# Aquila-2018-Under-DESKTOP-4DKEQLF.net
KiCad netlist of a schematic drawn in EAGLE
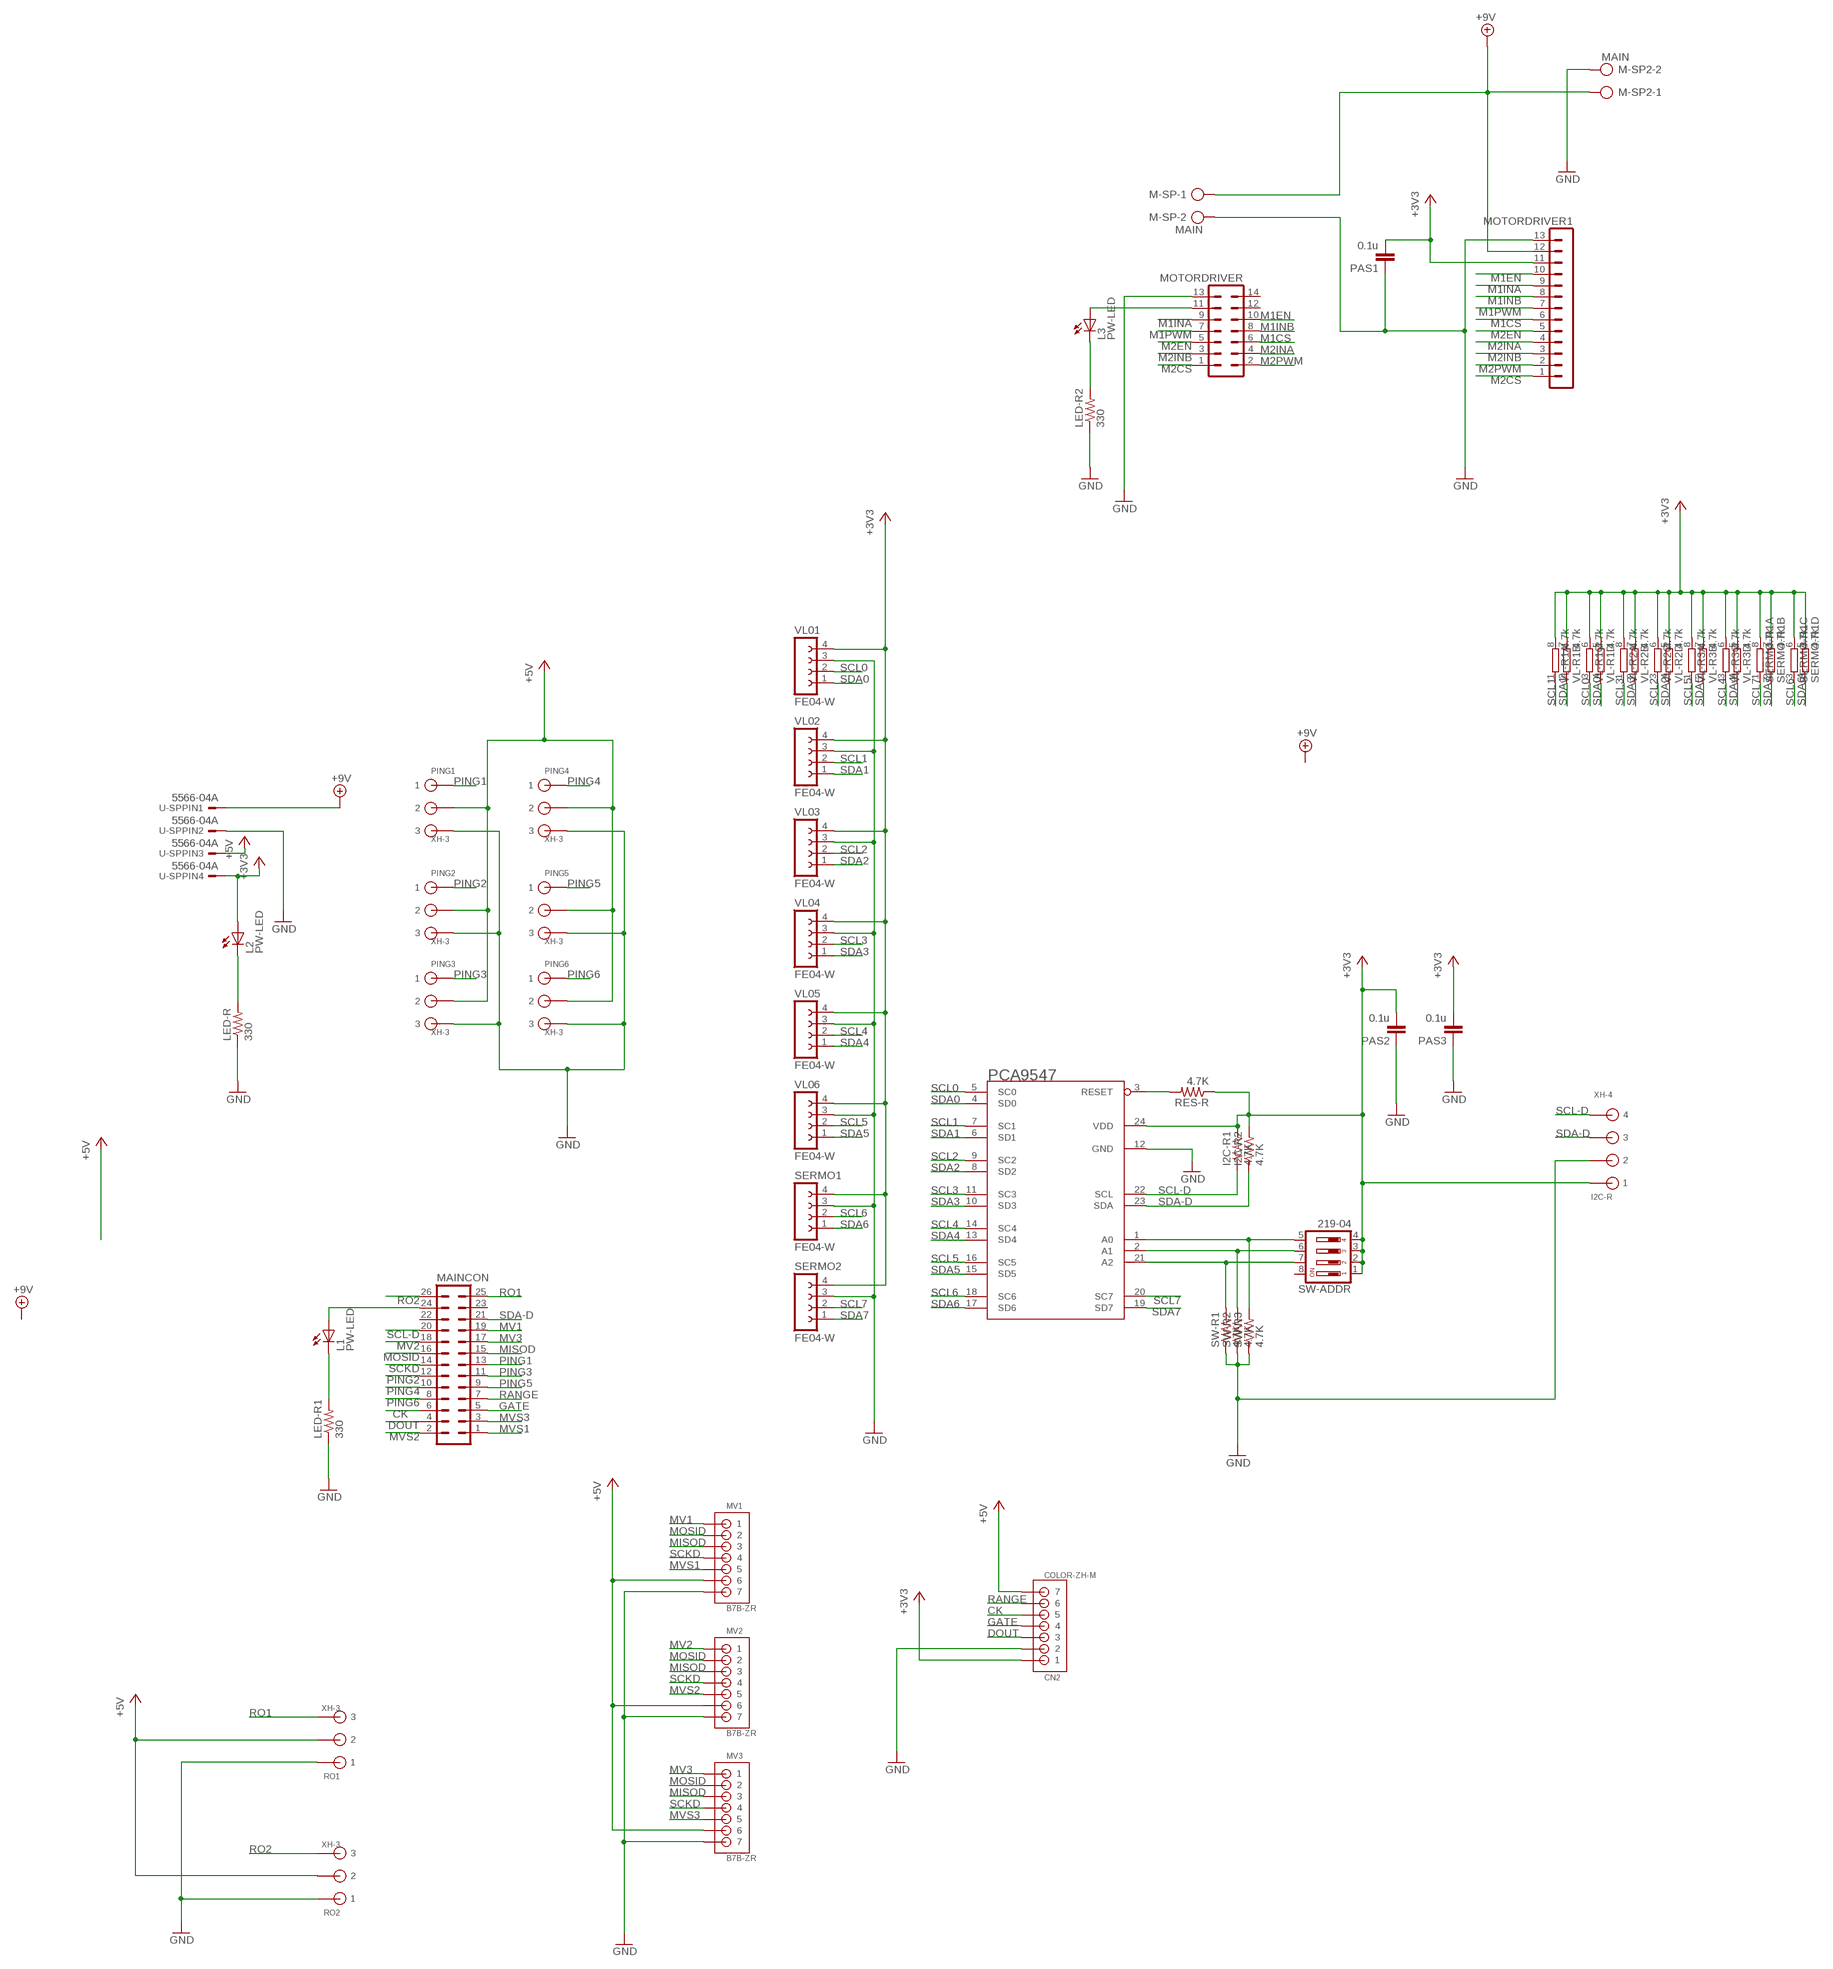
[diagram p0: schematic, sheet 1]

(export (version "E")
  (design (tool "Eeschema 10.0.6"))
  (components
    (comp (ref "CN2")
      (value "COLOR-ZH-M")
      (footprint "eagle-import:B7B-ZR")
      (libsource (lib "eagle-import") (part "B7B-ZR"))
    )
    (comp (ref "I2C-R")
      (value "XH-4")
      (footprint "eagle-import:CON4")
      (libsource (lib "eagle-import") (part "XH-4"))
    )
    (comp (ref "I2C-R1")
      (value "4.7K")
      (footprint "eagle-import:R0805")
      (libsource (lib "eagle-import") (part "R-US_R0805"))
    )
    (comp (ref "I2C-R2")
      (value "4.7K")
      (footprint "eagle-import:R0805")
      (libsource (lib "eagle-import") (part "R-US_R0805"))
    )
    (comp (ref "L1")
      (value "PW-LED")
      (footprint "eagle-import:CHIPLED_0805")
      (libsource (lib "eagle-import") (part "LEDCHIPLED_0805"))
    )
    (comp (ref "L2")
      (value "PW-LED")
      (footprint "eagle-import:CHIPLED_0805")
      (libsource (lib "eagle-import") (part "LEDCHIPLED_0805"))
    )
    (comp (ref "L3")
      (value "PW-LED")
      (footprint "eagle-import:CHIPLED_0805")
      (libsource (lib "eagle-import") (part "LEDCHIPLED_0805"))
    )
    (comp (ref "LED-R")
      (value "330")
      (footprint "eagle-import:R0805")
      (libsource (lib "eagle-import") (part "R-US_R0805"))
    )
    (comp (ref "LED-R1")
      (value "330")
      (footprint "eagle-import:R0805")
      (libsource (lib "eagle-import") (part "R-US_R0805"))
    )
    (comp (ref "LED-R2")
      (value "330")
      (footprint "eagle-import:R0805")
      (libsource (lib "eagle-import") (part "R-US_R0805"))
    )
    (comp (ref "M-SP")
      (value "MAIN")
      (footprint "eagle-import:AK500_2")
      (libsource (lib "eagle-import") (part "AK500/2"))
    )
    (comp (ref "M-SP2")
      (value "MAIN")
      (footprint "eagle-import:AK500_2")
      (libsource (lib "eagle-import") (part "AK500/2"))
    )
    (comp (ref "MAINCON")
      (value "ML26")
      (footprint "eagle-import:ML26")
      (libsource (lib "eagle-import") (part "ML26"))
    )
    (comp (ref "MOTORDRIVER")
      (value "ML14")
      (footprint "eagle-import:ML14")
      (libsource (lib "eagle-import") (part "ML14"))
    )
    (comp (ref "MOTORDRIVER1")
      (value "MA13-1")
      (footprint "eagle-import:MA13-1")
      (libsource (lib "eagle-import") (part "MA13-1"))
    )
    (comp (ref "MV1")
      (value "B7B-ZR")
      (footprint "eagle-import:B7B-ZR")
      (libsource (lib "eagle-import") (part "B7B-ZR"))
    )
    (comp (ref "MV2")
      (value "B7B-ZR")
      (footprint "eagle-import:B7B-ZR")
      (libsource (lib "eagle-import") (part "B7B-ZR"))
    )
    (comp (ref "MV3")
      (value "B7B-ZR")
      (footprint "eagle-import:B7B-ZR")
      (libsource (lib "eagle-import") (part "B7B-ZR"))
    )
    (comp (ref "PAS1")
      (value "0.1u")
      (footprint "eagle-import:C0805")
      (fields (field (name "SPICEPREFIX") "B"))
      (libsource (lib "eagle-import") (part "C-EUC0805"))
    )
    (comp (ref "PAS2")
      (value "0.1u")
      (footprint "eagle-import:C0805")
      (fields (field (name "SPICEPREFIX") "B"))
      (libsource (lib "eagle-import") (part "C-EUC0805"))
    )
    (comp (ref "PAS3")
      (value "0.1u")
      (footprint "eagle-import:C0805")
      (fields (field (name "SPICEPREFIX") "B"))
      (libsource (lib "eagle-import") (part "C-EUC0805"))
    )
    (comp (ref "PCA9547")
      (value "PCA9547")
      (footprint "eagle-import:SO24L")
      (libsource (lib "eagle-import") (part "PCA9547"))
    )
    (comp (ref "PING1")
      (value "XH-3")
      (footprint "eagle-import:CON3")
      (libsource (lib "eagle-import") (part "XH-3"))
    )
    (comp (ref "PING2")
      (value "XH-3")
      (footprint "eagle-import:CON3")
      (libsource (lib "eagle-import") (part "XH-3"))
    )
    (comp (ref "PING3")
      (value "XH-3")
      (footprint "eagle-import:CON3")
      (libsource (lib "eagle-import") (part "XH-3"))
    )
    (comp (ref "PING4")
      (value "XH-3")
      (footprint "eagle-import:CON3")
      (libsource (lib "eagle-import") (part "XH-3"))
    )
    (comp (ref "PING5")
      (value "XH-3")
      (footprint "eagle-import:CON3")
      (libsource (lib "eagle-import") (part "XH-3"))
    )
    (comp (ref "PING6")
      (value "XH-3")
      (footprint "eagle-import:CON3")
      (libsource (lib "eagle-import") (part "XH-3"))
    )
    (comp (ref "RES-R")
      (value "4.7K")
      (footprint "eagle-import:R0805")
      (libsource (lib "eagle-import") (part "R-US_R0805"))
    )
    (comp (ref "RO1")
      (value "XH-3")
      (footprint "eagle-import:CON3")
      (libsource (lib "eagle-import") (part "forprint_XH-3"))
    )
    (comp (ref "RO2")
      (value "XH-3")
      (footprint "eagle-import:CON3")
      (libsource (lib "eagle-import") (part "forprint_XH-3"))
    )
    (comp (ref "SERMO-R1")
      (value "4.7k")
      (footprint "eagle-import:EXB28V")
      (libsource (lib "eagle-import") (part "4R-NEXB28V"))
    )
    (comp (ref "SERMO1")
      (value "FE04-W")
      (footprint "eagle-import:FE04-W")
      (libsource (lib "eagle-import") (part "FE04-W"))
    )
    (comp (ref "SERMO2")
      (value "FE04-W")
      (footprint "eagle-import:FE04-W")
      (libsource (lib "eagle-import") (part "FE04-W"))
    )
    (comp (ref "SW-ADDR")
      (value "219-04")
      (footprint "eagle-import:CTS-219-04")
      (libsource (lib "eagle-import") (part "219-04"))
    )
    (comp (ref "SW-R1")
      (value "4.7K")
      (footprint "eagle-import:R0805")
      (libsource (lib "eagle-import") (part "R-US_R0805"))
    )
    (comp (ref "SW-R2")
      (value "4.7K")
      (footprint "eagle-import:R0805")
      (libsource (lib "eagle-import") (part "R-US_R0805"))
    )
    (comp (ref "SW-R3")
      (value "4.7K")
      (footprint "eagle-import:R0805")
      (libsource (lib "eagle-import") (part "R-US_R0805"))
    )
    (comp (ref "U-SP")
      (value "5566-04A")
      (footprint "eagle-import:5566-04A")
      (libsource (lib "eagle-import") (part "5566-04A"))
    )
    (comp (ref "VL-R1")
      (value "4.7k")
      (footprint "eagle-import:EXB28V")
      (libsource (lib "eagle-import") (part "4R-NEXB28V"))
    )
    (comp (ref "VL-R2")
      (value "4.7k")
      (footprint "eagle-import:EXB28V")
      (libsource (lib "eagle-import") (part "4R-NEXB28V"))
    )
    (comp (ref "VL-R3")
      (value "4.7k")
      (footprint "eagle-import:EXB28V")
      (libsource (lib "eagle-import") (part "4R-NEXB28V"))
    )
    (comp (ref "VL01")
      (value "FE04-W")
      (footprint "eagle-import:FE04-W")
      (libsource (lib "eagle-import") (part "FE04-W"))
    )
    (comp (ref "VL02")
      (value "FE04-W")
      (footprint "eagle-import:FE04-W")
      (libsource (lib "eagle-import") (part "FE04-W"))
    )
    (comp (ref "VL03")
      (value "FE04-W")
      (footprint "eagle-import:FE04-W")
      (libsource (lib "eagle-import") (part "FE04-W"))
    )
    (comp (ref "VL04")
      (value "FE04-W")
      (footprint "eagle-import:FE04-W")
      (libsource (lib "eagle-import") (part "FE04-W"))
    )
    (comp (ref "VL05")
      (value "FE04-W")
      (footprint "eagle-import:FE04-W")
      (libsource (lib "eagle-import") (part "FE04-W"))
    )
    (comp (ref "VL06")
      (value "FE04-W")
      (footprint "eagle-import:FE04-W")
      (libsource (lib "eagle-import") (part "FE04-W"))
    )
  )
  (nets
    (net (code "1") (name "+3V3") (class "Default")
      (node (ref "CN2") (pin "1") (pinfunction "1_1") (pintype "bidirectional"))
      (node (ref "I2C-R") (pin "P$1") (pinfunction "1_P$1") (pintype "bidirectional"))
      (node (ref "I2C-R1") (pin "2") (pinfunction "2_2") (pintype "passive"))
      (node (ref "I2C-R2") (pin "2") (pinfunction "2_2") (pintype "passive"))
      (node (ref "L2") (pin "A") (pinfunction "A_A") (pintype "passive"))
      (node (ref "MOTORDRIVER1") (pin "11") (pinfunction "11_11") (pintype "passive"))
      (node (ref "PAS1") (pin "2") (pinfunction "2_2") (pintype "passive"))
      (node (ref "PAS2") (pin "2") (pinfunction "2_2") (pintype "passive"))
      (node (ref "PAS3") (pin "2") (pinfunction "2_2") (pintype "passive"))
      (node (ref "PCA9547") (pin "24") (pinfunction "VDD_24") (pintype "power_in"))
      (node (ref "RES-R") (pin "1") (pinfunction "1_1") (pintype "passive"))
      (node (ref "SERMO-R1") (pin "5") (pinfunction "2_5") (pintype "passive"))
      (node (ref "SERMO-R1") (pin "6") (pinfunction "2_6") (pintype "passive"))
      (node (ref "SERMO-R1") (pin "7") (pinfunction "2_7") (pintype "passive"))
      (node (ref "SERMO-R1") (pin "8") (pinfunction "2_8") (pintype "passive"))
      (node (ref "SERMO1") (pin "4") (pinfunction "4_4") (pintype "passive"))
      (node (ref "SERMO2") (pin "4") (pinfunction "4_4") (pintype "passive"))
      (node (ref "SW-ADDR") (pin "1") (pinfunction "1_1") (pintype "passive"))
      (node (ref "SW-ADDR") (pin "2") (pinfunction "2_2") (pintype "passive"))
      (node (ref "SW-ADDR") (pin "3") (pinfunction "3_3") (pintype "passive"))
      (node (ref "SW-ADDR") (pin "4") (pinfunction "4_4") (pintype "passive"))
      (node (ref "U-SP") (pin "4") (pinfunction "S_4") (pintype "passive"))
      (node (ref "VL-R1") (pin "5") (pinfunction "2_5") (pintype "passive"))
      (node (ref "VL-R1") (pin "6") (pinfunction "2_6") (pintype "passive"))
      (node (ref "VL-R1") (pin "7") (pinfunction "2_7") (pintype "passive"))
      (node (ref "VL-R1") (pin "8") (pinfunction "2_8") (pintype "passive"))
      (node (ref "VL-R2") (pin "5") (pinfunction "2_5") (pintype "passive"))
      (node (ref "VL-R2") (pin "6") (pinfunction "2_6") (pintype "passive"))
      (node (ref "VL-R2") (pin "7") (pinfunction "2_7") (pintype "passive"))
      (node (ref "VL-R2") (pin "8") (pinfunction "2_8") (pintype "passive"))
      (node (ref "VL-R3") (pin "5") (pinfunction "2_5") (pintype "passive"))
      (node (ref "VL-R3") (pin "6") (pinfunction "2_6") (pintype "passive"))
      (node (ref "VL-R3") (pin "7") (pinfunction "2_7") (pintype "passive"))
      (node (ref "VL-R3") (pin "8") (pinfunction "2_8") (pintype "passive"))
      (node (ref "VL01") (pin "4") (pinfunction "4_4") (pintype "passive"))
      (node (ref "VL02") (pin "4") (pinfunction "4_4") (pintype "passive"))
      (node (ref "VL03") (pin "4") (pinfunction "4_4") (pintype "passive"))
      (node (ref "VL04") (pin "4") (pinfunction "4_4") (pintype "passive"))
      (node (ref "VL05") (pin "4") (pinfunction "4_4") (pintype "passive"))
      (node (ref "VL06") (pin "4") (pinfunction "4_4") (pintype "passive"))
    )
    (net (code "2") (name "+5V") (class "Default")
      (node (ref "CN2") (pin "7") (pinfunction "7_7") (pintype "bidirectional"))
      (node (ref "MV1") (pin "6") (pinfunction "6_6") (pintype "bidirectional"))
      (node (ref "MV2") (pin "6") (pinfunction "6_6") (pintype "bidirectional"))
      (node (ref "MV3") (pin "6") (pinfunction "6_6") (pintype "bidirectional"))
      (node (ref "PING1") (pin "P$2") (pinfunction "2_P$2") (pintype "bidirectional"))
      (node (ref "PING2") (pin "P$2") (pinfunction "2_P$2") (pintype "bidirectional"))
      (node (ref "PING3") (pin "P$2") (pinfunction "2_P$2") (pintype "bidirectional"))
      (node (ref "PING4") (pin "P$2") (pinfunction "2_P$2") (pintype "bidirectional"))
      (node (ref "PING5") (pin "P$2") (pinfunction "2_P$2") (pintype "bidirectional"))
      (node (ref "PING6") (pin "P$2") (pinfunction "2_P$2") (pintype "bidirectional"))
      (node (ref "RO1") (pin "P$2") (pinfunction "2_P$2") (pintype "bidirectional"))
      (node (ref "RO2") (pin "P$2") (pinfunction "2_P$2") (pintype "bidirectional"))
      (node (ref "U-SP") (pin "3") (pinfunction "S_3") (pintype "passive"))
    )
    (net (code "3") (name "+9V") (class "Default")
      (node (ref "M-SP") (pin "1") (pinfunction "KL_1") (pintype "passive"))
      (node (ref "M-SP2") (pin "1") (pinfunction "KL_1") (pintype "passive"))
      (node (ref "MOTORDRIVER1") (pin "12") (pinfunction "12_12") (pintype "passive"))
      (node (ref "U-SP") (pin "1") (pinfunction "S_1") (pintype "passive"))
    )
    (net (code "4") (name "/CK") (class "Default")
      (node (ref "CN2") (pin "5") (pinfunction "5_5") (pintype "bidirectional"))
      (node (ref "MAINCON") (pin "6") (pinfunction "6_6") (pintype "passive"))
    )
    (net (code "5") (name "/DOUT") (class "Default")
      (node (ref "CN2") (pin "3") (pinfunction "3_3") (pintype "bidirectional"))
      (node (ref "MAINCON") (pin "4") (pinfunction "4_4") (pintype "passive"))
    )
    (net (code "6") (name "/GATE") (class "Default")
      (node (ref "CN2") (pin "4") (pinfunction "4_4") (pintype "bidirectional"))
      (node (ref "MAINCON") (pin "5") (pinfunction "5_5") (pintype "passive"))
    )
    (net (code "7") (name "/M1CS") (class "Default")
      (node (ref "MOTORDRIVER") (pin "6") (pinfunction "6_6") (pintype "passive"))
      (node (ref "MOTORDRIVER1") (pin "6") (pinfunction "6_6") (pintype "passive"))
    )
    (net (code "8") (name "/M1EN") (class "Default")
      (node (ref "MOTORDRIVER") (pin "10") (pinfunction "10_10") (pintype "passive"))
      (node (ref "MOTORDRIVER1") (pin "10") (pinfunction "10_10") (pintype "passive"))
    )
    (net (code "9") (name "/M1INA") (class "Default")
      (node (ref "MOTORDRIVER") (pin "9") (pinfunction "9_9") (pintype "passive"))
      (node (ref "MOTORDRIVER1") (pin "9") (pinfunction "9_9") (pintype "passive"))
    )
    (net (code "10") (name "/M1INB") (class "Default")
      (node (ref "MOTORDRIVER") (pin "8") (pinfunction "8_8") (pintype "passive"))
      (node (ref "MOTORDRIVER1") (pin "8") (pinfunction "8_8") (pintype "passive"))
    )
    (net (code "11") (name "/M1PWM") (class "Default")
      (node (ref "MOTORDRIVER") (pin "7") (pinfunction "7_7") (pintype "passive"))
      (node (ref "MOTORDRIVER1") (pin "7") (pinfunction "7_7") (pintype "passive"))
    )
    (net (code "12") (name "/M2CS") (class "Default")
      (node (ref "MOTORDRIVER") (pin "1") (pinfunction "1_1") (pintype "passive"))
      (node (ref "MOTORDRIVER1") (pin "1") (pinfunction "1_1") (pintype "passive"))
    )
    (net (code "13") (name "/M2EN") (class "Default")
      (node (ref "MOTORDRIVER") (pin "5") (pinfunction "5_5") (pintype "passive"))
      (node (ref "MOTORDRIVER1") (pin "5") (pinfunction "5_5") (pintype "passive"))
    )
    (net (code "14") (name "/M2INA") (class "Default")
      (node (ref "MOTORDRIVER") (pin "4") (pinfunction "4_4") (pintype "passive"))
      (node (ref "MOTORDRIVER1") (pin "4") (pinfunction "4_4") (pintype "passive"))
    )
    (net (code "15") (name "/M2INB") (class "Default")
      (node (ref "MOTORDRIVER") (pin "3") (pinfunction "3_3") (pintype "passive"))
      (node (ref "MOTORDRIVER1") (pin "3") (pinfunction "3_3") (pintype "passive"))
    )
    (net (code "16") (name "/M2PWM") (class "Default")
      (node (ref "MOTORDRIVER") (pin "2") (pinfunction "2_2") (pintype "passive"))
      (node (ref "MOTORDRIVER1") (pin "2") (pinfunction "2_2") (pintype "passive"))
    )
    (net (code "17") (name "/MISOD") (class "Default")
      (node (ref "MAINCON") (pin "15") (pinfunction "15_15") (pintype "passive"))
      (node (ref "MV1") (pin "3") (pinfunction "3_3") (pintype "bidirectional"))
      (node (ref "MV2") (pin "3") (pinfunction "3_3") (pintype "bidirectional"))
      (node (ref "MV3") (pin "3") (pinfunction "3_3") (pintype "bidirectional"))
    )
    (net (code "18") (name "/MOSID") (class "Default")
      (node (ref "MAINCON") (pin "16") (pinfunction "16_16") (pintype "passive"))
      (node (ref "MV1") (pin "2") (pinfunction "2_2") (pintype "bidirectional"))
      (node (ref "MV2") (pin "2") (pinfunction "2_2") (pintype "bidirectional"))
      (node (ref "MV3") (pin "2") (pinfunction "2_2") (pintype "bidirectional"))
    )
    (net (code "19") (name "/MV1") (class "Default")
      (node (ref "MAINCON") (pin "19") (pinfunction "19_19") (pintype "passive"))
      (node (ref "MV1") (pin "1") (pinfunction "1_1") (pintype "bidirectional"))
    )
    (net (code "20") (name "/MV2") (class "Default")
      (node (ref "MAINCON") (pin "18") (pinfunction "18_18") (pintype "passive"))
      (node (ref "MV2") (pin "1") (pinfunction "1_1") (pintype "bidirectional"))
    )
    (net (code "21") (name "/MV3") (class "Default")
      (node (ref "MAINCON") (pin "17") (pinfunction "17_17") (pintype "passive"))
      (node (ref "MV3") (pin "1") (pinfunction "1_1") (pintype "bidirectional"))
    )
    (net (code "22") (name "/MVS1") (class "Default")
      (node (ref "MAINCON") (pin "1") (pinfunction "1_1") (pintype "passive"))
      (node (ref "MV1") (pin "5") (pinfunction "5_5") (pintype "bidirectional"))
    )
    (net (code "23") (name "/MVS2") (class "Default")
      (node (ref "MAINCON") (pin "2") (pinfunction "2_2") (pintype "passive"))
      (node (ref "MV2") (pin "5") (pinfunction "5_5") (pintype "bidirectional"))
    )
    (net (code "24") (name "/MVS3") (class "Default")
      (node (ref "MAINCON") (pin "3") (pinfunction "3_3") (pintype "passive"))
      (node (ref "MV3") (pin "5") (pinfunction "5_5") (pintype "bidirectional"))
    )
    (net (code "25") (name "/PING1") (class "Default")
      (node (ref "MAINCON") (pin "13") (pinfunction "13_13") (pintype "passive"))
      (node (ref "PING1") (pin "P$1") (pinfunction "1_P$1") (pintype "bidirectional"))
    )
    (net (code "26") (name "/PING2") (class "Default")
      (node (ref "MAINCON") (pin "12") (pinfunction "12_12") (pintype "passive"))
      (node (ref "PING2") (pin "P$1") (pinfunction "1_P$1") (pintype "bidirectional"))
    )
    (net (code "27") (name "/PING3") (class "Default")
      (node (ref "MAINCON") (pin "11") (pinfunction "11_11") (pintype "passive"))
      (node (ref "PING3") (pin "P$1") (pinfunction "1_P$1") (pintype "bidirectional"))
    )
    (net (code "28") (name "/PING4") (class "Default")
      (node (ref "MAINCON") (pin "10") (pinfunction "10_10") (pintype "passive"))
      (node (ref "PING4") (pin "P$1") (pinfunction "1_P$1") (pintype "bidirectional"))
    )
    (net (code "29") (name "/PING5") (class "Default")
      (node (ref "MAINCON") (pin "9") (pinfunction "9_9") (pintype "passive"))
      (node (ref "PING5") (pin "P$1") (pinfunction "1_P$1") (pintype "bidirectional"))
    )
    (net (code "30") (name "/PING6") (class "Default")
      (node (ref "MAINCON") (pin "8") (pinfunction "8_8") (pintype "passive"))
      (node (ref "PING6") (pin "P$1") (pinfunction "1_P$1") (pintype "bidirectional"))
    )
    (net (code "31") (name "/RANGE") (class "Default")
      (node (ref "CN2") (pin "6") (pinfunction "6_6") (pintype "bidirectional"))
      (node (ref "MAINCON") (pin "7") (pinfunction "7_7") (pintype "passive"))
    )
    (net (code "32") (name "/RO1") (class "Default")
      (node (ref "MAINCON") (pin "25") (pinfunction "25_25") (pintype "passive"))
      (node (ref "RO1") (pin "P$3") (pinfunction "3_P$3") (pintype "bidirectional"))
    )
    (net (code "33") (name "/RO2") (class "Default")
      (node (ref "MAINCON") (pin "26") (pinfunction "26_26") (pintype "passive"))
      (node (ref "RO2") (pin "P$3") (pinfunction "3_P$3") (pintype "bidirectional"))
    )
    (net (code "34") (name "/SCKD") (class "Default")
      (node (ref "MAINCON") (pin "14") (pinfunction "14_14") (pintype "passive"))
      (node (ref "MV1") (pin "4") (pinfunction "4_4") (pintype "bidirectional"))
      (node (ref "MV2") (pin "4") (pinfunction "4_4") (pintype "bidirectional"))
      (node (ref "MV3") (pin "4") (pinfunction "4_4") (pintype "bidirectional"))
    )
    (net (code "35") (name "/SCL-D") (class "Default")
      (node (ref "I2C-R") (pin "P$4") (pinfunction "4_P$4") (pintype "bidirectional"))
      (node (ref "I2C-R1") (pin "1") (pinfunction "1_1") (pintype "passive"))
      (node (ref "MAINCON") (pin "20") (pinfunction "20_20") (pintype "passive"))
      (node (ref "PCA9547") (pin "22") (pinfunction "SCL_22") (pintype "bidirectional"))
    )
    (net (code "36") (name "/SCL0") (class "Default")
      (node (ref "PCA9547") (pin "5") (pinfunction "SC0_5") (pintype "bidirectional"))
      (node (ref "VL-R1") (pin "3") (pinfunction "1_3") (pintype "passive"))
      (node (ref "VL01") (pin "2") (pinfunction "2_2") (pintype "passive"))
    )
    (net (code "37") (name "/SCL1") (class "Default")
      (node (ref "PCA9547") (pin "7") (pinfunction "SC1_7") (pintype "bidirectional"))
      (node (ref "VL-R1") (pin "1") (pinfunction "1_1") (pintype "passive"))
      (node (ref "VL02") (pin "2") (pinfunction "2_2") (pintype "passive"))
    )
    (net (code "38") (name "/SCL2") (class "Default")
      (node (ref "PCA9547") (pin "9") (pinfunction "SC2_9") (pintype "bidirectional"))
      (node (ref "VL-R2") (pin "3") (pinfunction "1_3") (pintype "passive"))
      (node (ref "VL03") (pin "2") (pinfunction "2_2") (pintype "passive"))
    )
    (net (code "39") (name "/SCL3") (class "Default")
      (node (ref "PCA9547") (pin "11") (pinfunction "SC3_11") (pintype "bidirectional"))
      (node (ref "VL-R2") (pin "1") (pinfunction "1_1") (pintype "passive"))
      (node (ref "VL04") (pin "2") (pinfunction "2_2") (pintype "passive"))
    )
    (net (code "40") (name "/SCL4") (class "Default")
      (node (ref "PCA9547") (pin "14") (pinfunction "SC4_14") (pintype "bidirectional"))
      (node (ref "VL-R3") (pin "3") (pinfunction "1_3") (pintype "passive"))
      (node (ref "VL05") (pin "2") (pinfunction "2_2") (pintype "passive"))
    )
    (net (code "41") (name "/SCL5") (class "Default")
      (node (ref "PCA9547") (pin "16") (pinfunction "SC5_16") (pintype "bidirectional"))
      (node (ref "VL-R3") (pin "1") (pinfunction "1_1") (pintype "passive"))
      (node (ref "VL06") (pin "2") (pinfunction "2_2") (pintype "passive"))
    )
    (net (code "42") (name "/SCL6") (class "Default")
      (node (ref "PCA9547") (pin "18") (pinfunction "SC6_18") (pintype "bidirectional"))
      (node (ref "SERMO-R1") (pin "3") (pinfunction "1_3") (pintype "passive"))
      (node (ref "SERMO1") (pin "2") (pinfunction "2_2") (pintype "passive"))
    )
    (net (code "43") (name "/SCL7") (class "Default")
      (node (ref "PCA9547") (pin "20") (pinfunction "SC7_20") (pintype "bidirectional"))
      (node (ref "SERMO-R1") (pin "1") (pinfunction "1_1") (pintype "passive"))
      (node (ref "SERMO2") (pin "2") (pinfunction "2_2") (pintype "passive"))
    )
    (net (code "44") (name "/SDA-D") (class "Default")
      (node (ref "I2C-R") (pin "P$3") (pinfunction "3_P$3") (pintype "bidirectional"))
      (node (ref "I2C-R2") (pin "1") (pinfunction "1_1") (pintype "passive"))
      (node (ref "MAINCON") (pin "21") (pinfunction "21_21") (pintype "passive"))
      (node (ref "PCA9547") (pin "23") (pinfunction "SDA_23") (pintype "bidirectional"))
    )
    (net (code "45") (name "/SDA0") (class "Default")
      (node (ref "PCA9547") (pin "4") (pinfunction "SD0_4") (pintype "bidirectional"))
      (node (ref "VL-R1") (pin "4") (pinfunction "1_4") (pintype "passive"))
      (node (ref "VL01") (pin "1") (pinfunction "1_1") (pintype "passive"))
    )
    (net (code "46") (name "/SDA1") (class "Default")
      (node (ref "PCA9547") (pin "6") (pinfunction "SD1_6") (pintype "bidirectional"))
      (node (ref "VL-R1") (pin "2") (pinfunction "1_2") (pintype "passive"))
      (node (ref "VL02") (pin "1") (pinfunction "1_1") (pintype "passive"))
    )
    (net (code "47") (name "/SDA2") (class "Default")
      (node (ref "PCA9547") (pin "8") (pinfunction "SD2_8") (pintype "bidirectional"))
      (node (ref "VL-R2") (pin "4") (pinfunction "1_4") (pintype "passive"))
      (node (ref "VL03") (pin "1") (pinfunction "1_1") (pintype "passive"))
    )
    (net (code "48") (name "/SDA3") (class "Default")
      (node (ref "PCA9547") (pin "10") (pinfunction "SD3_10") (pintype "bidirectional"))
      (node (ref "VL-R2") (pin "2") (pinfunction "1_2") (pintype "passive"))
      (node (ref "VL04") (pin "1") (pinfunction "1_1") (pintype "passive"))
    )
    (net (code "49") (name "/SDA4") (class "Default")
      (node (ref "PCA9547") (pin "13") (pinfunction "SD4_13") (pintype "bidirectional"))
      (node (ref "VL-R3") (pin "4") (pinfunction "1_4") (pintype "passive"))
      (node (ref "VL05") (pin "1") (pinfunction "1_1") (pintype "passive"))
    )
    (net (code "50") (name "/SDA5") (class "Default")
      (node (ref "PCA9547") (pin "15") (pinfunction "SD5_15") (pintype "bidirectional"))
      (node (ref "VL-R3") (pin "2") (pinfunction "1_2") (pintype "passive"))
      (node (ref "VL06") (pin "1") (pinfunction "1_1") (pintype "passive"))
    )
    (net (code "51") (name "/SDA6") (class "Default")
      (node (ref "PCA9547") (pin "17") (pinfunction "SD6_17") (pintype "bidirectional"))
      (node (ref "SERMO-R1") (pin "4") (pinfunction "1_4") (pintype "passive"))
      (node (ref "SERMO1") (pin "1") (pinfunction "1_1") (pintype "passive"))
    )
    (net (code "52") (name "/SDA7") (class "Default")
      (node (ref "PCA9547") (pin "19") (pinfunction "SD7_19") (pintype "bidirectional"))
      (node (ref "SERMO-R1") (pin "2") (pinfunction "1_2") (pintype "passive"))
      (node (ref "SERMO2") (pin "1") (pinfunction "1_1") (pintype "passive"))
    )
    (net (code "53") (name "GND") (class "Default")
      (node (ref "CN2") (pin "2") (pinfunction "2_2") (pintype "bidirectional"))
      (node (ref "I2C-R") (pin "P$2") (pinfunction "2_P$2") (pintype "bidirectional"))
      (node (ref "LED-R") (pin "1") (pinfunction "1_1") (pintype "passive"))
      (node (ref "LED-R1") (pin "1") (pinfunction "1_1") (pintype "passive"))
      (node (ref "LED-R2") (pin "1") (pinfunction "1_1") (pintype "passive"))
      (node (ref "M-SP") (pin "2") (pinfunction "KL_2") (pintype "passive"))
      (node (ref "M-SP2") (pin "2") (pinfunction "KL_2") (pintype "passive"))
      (node (ref "MOTORDRIVER") (pin "13") (pinfunction "13_13") (pintype "passive"))
      (node (ref "MOTORDRIVER1") (pin "13") (pinfunction "13_13") (pintype "passive"))
      (node (ref "MV1") (pin "7") (pinfunction "7_7") (pintype "bidirectional"))
      (node (ref "MV2") (pin "7") (pinfunction "7_7") (pintype "bidirectional"))
      (node (ref "MV3") (pin "7") (pinfunction "7_7") (pintype "bidirectional"))
      (node (ref "PAS1") (pin "1") (pinfunction "1_1") (pintype "passive"))
      (node (ref "PAS2") (pin "1") (pinfunction "1_1") (pintype "passive"))
      (node (ref "PAS3") (pin "1") (pinfunction "1_1") (pintype "passive"))
      (node (ref "PCA9547") (pin "12") (pinfunction "GND_12") (pintype "power_in"))
      (node (ref "PING1") (pin "P$3") (pinfunction "3_P$3") (pintype "bidirectional"))
      (node (ref "PING2") (pin "P$3") (pinfunction "3_P$3") (pintype "bidirectional"))
      (node (ref "PING3") (pin "P$3") (pinfunction "3_P$3") (pintype "bidirectional"))
      (node (ref "PING4") (pin "P$3") (pinfunction "3_P$3") (pintype "bidirectional"))
      (node (ref "PING5") (pin "P$3") (pinfunction "3_P$3") (pintype "bidirectional"))
      (node (ref "PING6") (pin "P$3") (pinfunction "3_P$3") (pintype "bidirectional"))
      (node (ref "RO1") (pin "P$1") (pinfunction "1_P$1") (pintype "bidirectional"))
      (node (ref "RO2") (pin "P$1") (pinfunction "1_P$1") (pintype "bidirectional"))
      (node (ref "SERMO1") (pin "3") (pinfunction "3_3") (pintype "passive"))
      (node (ref "SERMO2") (pin "3") (pinfunction "3_3") (pintype "passive"))
      (node (ref "SW-R1") (pin "1") (pinfunction "1_1") (pintype "passive"))
      (node (ref "SW-R2") (pin "1") (pinfunction "1_1") (pintype "passive"))
      (node (ref "SW-R3") (pin "1") (pinfunction "1_1") (pintype "passive"))
      (node (ref "U-SP") (pin "2") (pinfunction "S_2") (pintype "passive"))
      (node (ref "VL01") (pin "3") (pinfunction "3_3") (pintype "passive"))
      (node (ref "VL02") (pin "3") (pinfunction "3_3") (pintype "passive"))
      (node (ref "VL03") (pin "3") (pinfunction "3_3") (pintype "passive"))
      (node (ref "VL04") (pin "3") (pinfunction "3_3") (pintype "passive"))
      (node (ref "VL05") (pin "3") (pinfunction "3_3") (pintype "passive"))
      (node (ref "VL06") (pin "3") (pinfunction "3_3") (pintype "passive"))
    )
    (net (code "54") (name "Net-(L1-PadA)") (class "Default")
      (node (ref "L1") (pin "A") (pinfunction "A_A") (pintype "passive"))
      (node (ref "MAINCON") (pin "24") (pinfunction "24_24") (pintype "passive"))
    )
    (net (code "55") (name "Net-(L1-PadC)") (class "Default")
      (node (ref "L1") (pin "C") (pinfunction "C_C") (pintype "passive"))
      (node (ref "LED-R1") (pin "2") (pinfunction "2_2") (pintype "passive"))
    )
    (net (code "56") (name "Net-(L2-PadC)") (class "Default")
      (node (ref "L2") (pin "C") (pinfunction "C_C") (pintype "passive"))
      (node (ref "LED-R") (pin "2") (pinfunction "2_2") (pintype "passive"))
    )
    (net (code "57") (name "Net-(L3-PadA)") (class "Default")
      (node (ref "L3") (pin "A") (pinfunction "A_A") (pintype "passive"))
      (node (ref "MOTORDRIVER") (pin "11") (pinfunction "11_11") (pintype "passive"))
    )
    (net (code "58") (name "Net-(L3-PadC)") (class "Default")
      (node (ref "L3") (pin "C") (pinfunction "C_C") (pintype "passive"))
      (node (ref "LED-R2") (pin "2") (pinfunction "2_2") (pintype "passive"))
    )
    (net (code "59") (name "Net-(PCA9547-A0)") (class "Default")
      (node (ref "PCA9547") (pin "1") (pinfunction "A0_1") (pintype "input"))
      (node (ref "SW-ADDR") (pin "5") (pinfunction "5_5") (pintype "passive"))
      (node (ref "SW-R3") (pin "2") (pinfunction "2_2") (pintype "passive"))
    )
    (net (code "60") (name "Net-(PCA9547-A1)") (class "Default")
      (node (ref "PCA9547") (pin "2") (pinfunction "A1_2") (pintype "input"))
      (node (ref "SW-ADDR") (pin "6") (pinfunction "6_6") (pintype "passive"))
      (node (ref "SW-R2") (pin "2") (pinfunction "2_2") (pintype "passive"))
    )
    (net (code "61") (name "Net-(PCA9547-A2)") (class "Default")
      (node (ref "PCA9547") (pin "21") (pinfunction "A2_21") (pintype "input"))
      (node (ref "SW-ADDR") (pin "7") (pinfunction "7_7") (pintype "passive"))
      (node (ref "SW-R1") (pin "2") (pinfunction "2_2") (pintype "passive"))
    )
    (net (code "62") (name "Net-(PCA9547-RESET)") (class "Default")
      (node (ref "PCA9547") (pin "3") (pinfunction "RESET_3") (pintype "bidirectional"))
      (node (ref "RES-R") (pin "2") (pinfunction "2_2") (pintype "passive"))
    )
    (net (code "63") (name "unconnected-(MAINCON-Pad22)") (class "Default")
      (node (ref "MAINCON") (pin "22") (pinfunction "22_22") (pintype "passive"))
    )
    (net (code "64") (name "unconnected-(MAINCON-Pad23)") (class "Default")
      (node (ref "MAINCON") (pin "23") (pinfunction "23_23") (pintype "passive"))
    )
    (net (code "65") (name "unconnected-(MOTORDRIVER-Pad12)") (class "Default")
      (node (ref "MOTORDRIVER") (pin "12") (pinfunction "12_12") (pintype "passive"))
    )
    (net (code "66") (name "unconnected-(MOTORDRIVER-Pad14)") (class "Default")
      (node (ref "MOTORDRIVER") (pin "14") (pinfunction "14_14") (pintype "passive"))
    )
    (net (code "67") (name "unconnected-(SW-ADDR-Pad8)") (class "Default")
      (node (ref "SW-ADDR") (pin "8") (pinfunction "8_8") (pintype "passive"))
    )
  )
)
